# AutonomousBot_Shield.net
KiCad netlist of a schematic drawn in EAGLE
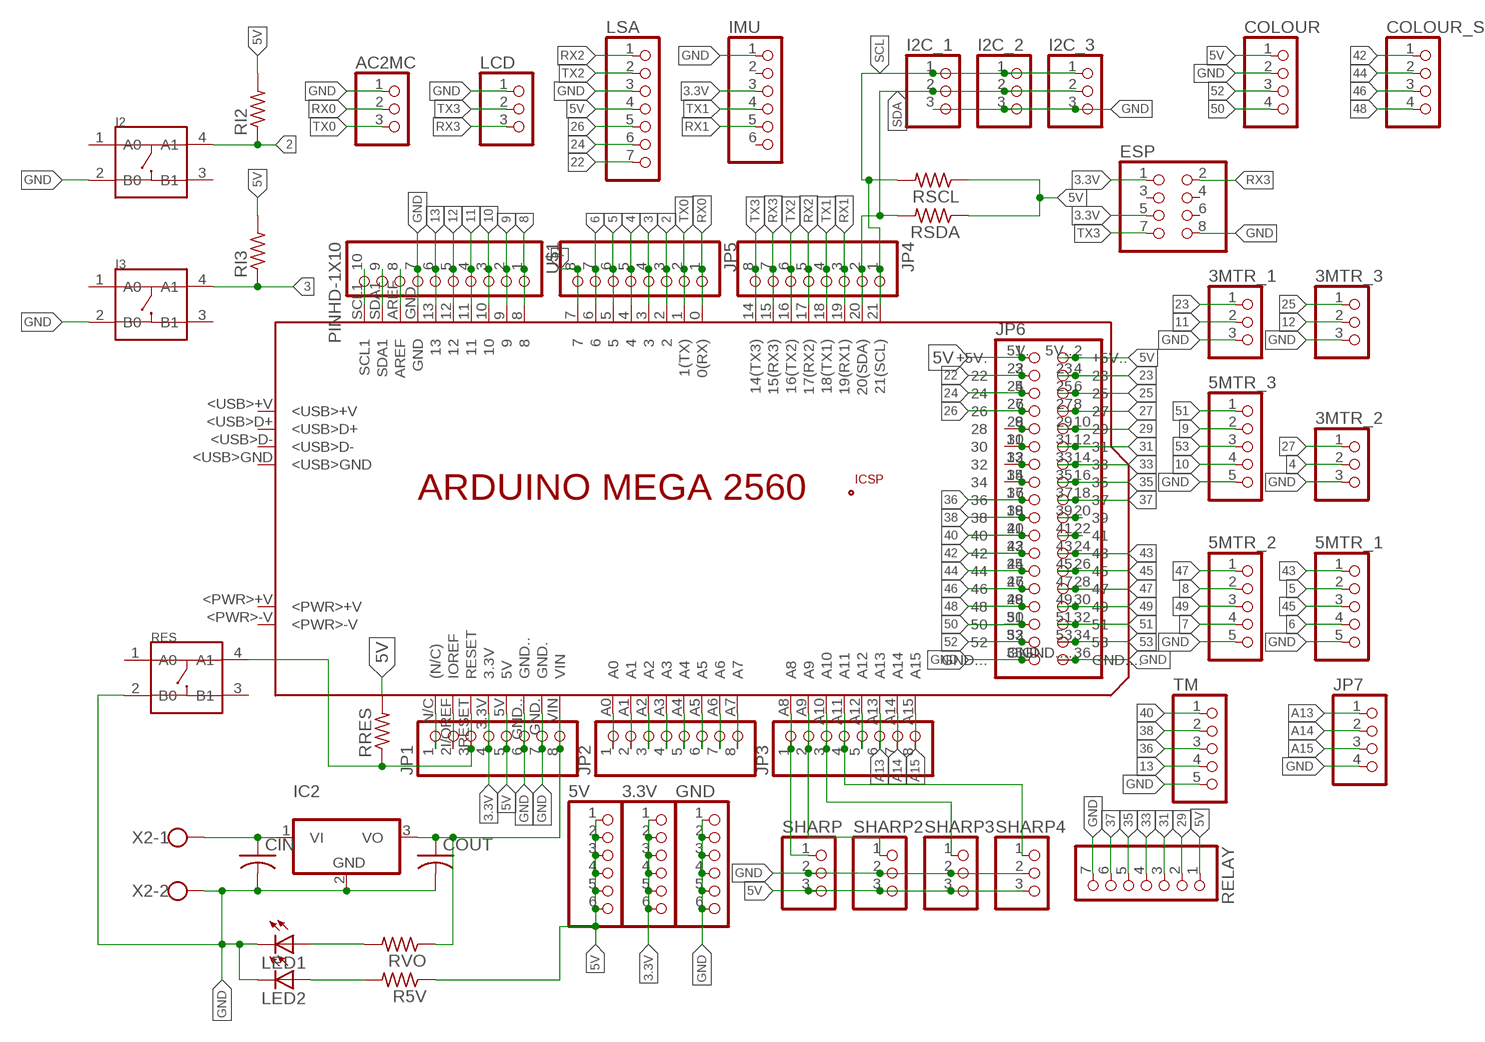
[diagram p0: schematic, sheet 1]

(export (version "E")
  (design (tool "Eeschema 10.0.6"))
  (components
    (comp (ref "3.3V")
      (value "PINHD-1X6")
      (footprint "eagle-import:1X06")
      (libsource (lib "eagle-import") (part "PINHD-1X6"))
    )
    (comp (ref "3MTR_1")
      (value "PINHD-1X3")
      (footprint "eagle-import:1X03")
      (libsource (lib "eagle-import") (part "pinhead_325_PINHD-1X3"))
    )
    (comp (ref "3MTR_2")
      (value "PINHD-1X3")
      (footprint "eagle-import:1X03")
      (libsource (lib "eagle-import") (part "pinhead_325_PINHD-1X3"))
    )
    (comp (ref "3MTR_3")
      (value "PINHD-1X3")
      (footprint "eagle-import:1X03")
      (libsource (lib "eagle-import") (part "pinhead_325_PINHD-1X3"))
    )
    (comp (ref "5MTR_1")
      (value "PINHD-1X5")
      (footprint "eagle-import:1X05")
      (libsource (lib "eagle-import") (part "pinhead_325_PINHD-1X5"))
    )
    (comp (ref "5MTR_2")
      (value "PINHD-1X5")
      (footprint "eagle-import:1X05")
      (libsource (lib "eagle-import") (part "pinhead_325_PINHD-1X5"))
    )
    (comp (ref "5MTR_3")
      (value "PINHD-1X5")
      (footprint "eagle-import:1X05")
      (libsource (lib "eagle-import") (part "pinhead_325_PINHD-1X5"))
    )
    (comp (ref "5V")
      (value "PINHD-1X6")
      (footprint "eagle-import:1X06")
      (libsource (lib "eagle-import") (part "PINHD-1X6"))
    )
    (comp (ref "AC2MC")
      (value "PINHD-1X3")
      (footprint "eagle-import:1X03")
      (libsource (lib "eagle-import") (part "PINHD-1X3"))
    )
    (comp (ref "CIN")
      (value "C-US025-024X044")
      (footprint "eagle-import:C025-024X044")
      (libsource (lib "eagle-import") (part "C-US025-024X044"))
    )
    (comp (ref "COLOUR")
      (value "PINHD-1X4")
      (footprint "eagle-import:1X04")
      (libsource (lib "eagle-import") (part "PINHD-1X4"))
    )
    (comp (ref "COLOUR_S")
      (value "PINHD-1X4")
      (footprint "eagle-import:1X04")
      (libsource (lib "eagle-import") (part "PINHD-1X4"))
    )
    (comp (ref "COUT")
      (value "C-US025-024X044")
      (footprint "eagle-import:C025-024X044")
      (libsource (lib "eagle-import") (part "C-US025-024X044"))
    )
    (comp (ref "ESP")
      (value "PINHD-2X4")
      (footprint "eagle-import:2X04")
      (libsource (lib "eagle-import") (part "PINHD-2X4"))
    )
    (comp (ref "GND")
      (value "PINHD-1X6")
      (footprint "eagle-import:1X06")
      (libsource (lib "eagle-import") (part "PINHD-1X6"))
    )
    (comp (ref "I2")
      (value "DIP-SWITCH-TACTILE-SPST-NO/TS-1109(4P-D6.0MM)'TS-1109'")
      (footprint "eagle-import:SW4-6.0X6.0X5.0MM")
      (libsource (lib "eagle-import") (part "DIP-SWITCH-TACTILE-SPST-NO/TS-1109(4P-D6.0MM)'TS-1109'"))
    )
    (comp (ref "I2C_1")
      (value "PINHD-1X3")
      (footprint "eagle-import:1X03")
      (libsource (lib "eagle-import") (part "PINHD-1X3"))
    )
    (comp (ref "I2C_2")
      (value "PINHD-1X3")
      (footprint "eagle-import:1X03")
      (libsource (lib "eagle-import") (part "PINHD-1X3"))
    )
    (comp (ref "I2C_3")
      (value "PINHD-1X3")
      (footprint "eagle-import:1X03")
      (libsource (lib "eagle-import") (part "PINHD-1X3"))
    )
    (comp (ref "I3")
      (value "DIP-SWITCH-TACTILE-SPST-NO/TS-1109(4P-D6.0MM)'TS-1109'")
      (footprint "eagle-import:SW4-6.0X6.0X5.0MM")
      (libsource (lib "eagle-import") (part "DIP-SWITCH-TACTILE-SPST-NO/TS-1109(4P-D6.0MM)'TS-1109'"))
    )
    (comp (ref "IC2")
      (value "7812TV")
      (footprint "eagle-import:TO220V")
      (libsource (lib "eagle-import") (part "78TV12"))
    )
    (comp (ref "IMU")
      (value "PINHD-1X6")
      (footprint "eagle-import:1X06")
      (libsource (lib "eagle-import") (part "PINHD-1X6"))
    )
    (comp (ref "JP1")
      (value "PINHD-1X8BIG")
      (footprint "eagle-import:1X08-BIG")
      (libsource (lib "eagle-import") (part "PINHD-1X8BIG"))
    )
    (comp (ref "JP2")
      (value "PINHD-1X8BIG")
      (footprint "eagle-import:1X08-BIG")
      (libsource (lib "eagle-import") (part "PINHD-1X8BIG"))
    )
    (comp (ref "JP3")
      (value "PINHD-1X8BIG")
      (footprint "eagle-import:1X08-BIG")
      (libsource (lib "eagle-import") (part "PINHD-1X8BIG"))
    )
    (comp (ref "JP4")
      (value "PINHD-1X8BIG")
      (footprint "eagle-import:1X08-BIG")
      (libsource (lib "eagle-import") (part "PINHD-1X8BIG"))
    )
    (comp (ref "JP5")
      (value "PINHD-1X8BIG")
      (footprint "eagle-import:1X08-BIG")
      (libsource (lib "eagle-import") (part "PINHD-1X8BIG"))
    )
    (comp (ref "JP6")
      (value "PINHD-2X18")
      (footprint "eagle-import:2X18")
      (libsource (lib "eagle-import") (part "PINHD-2X18"))
    )
    (comp (ref "JP7")
      (value "PINHD-1X4")
      (footprint "eagle-import:1X04")
      (libsource (lib "eagle-import") (part "PINHD-1X4"))
    )
    (comp (ref "LCD")
      (value "PINHD-1X3")
      (footprint "eagle-import:1X03")
      (libsource (lib "eagle-import") (part "PINHD-1X3"))
    )
    (comp (ref "LED1")
      (value "LED5MM")
      (footprint "eagle-import:LED5MM")
      (libsource (lib "eagle-import") (part "LED5MM"))
    )
    (comp (ref "LED2")
      (value "LED5MM")
      (footprint "eagle-import:LED5MM")
      (libsource (lib "eagle-import") (part "LED5MM"))
    )
    (comp (ref "LSA")
      (value "PINHD-1X7")
      (footprint "eagle-import:1X07")
      (libsource (lib "eagle-import") (part "PINHD-1X7"))
    )
    (comp (ref "PCB1")
      (value "ARDUINO_MEGA2560")
      (footprint "eagle-import:ARDUINO_MEGA2560")
      (libsource (lib "eagle-import") (part "ARDUINO_MEGA2560"))
    )
    (comp (ref "R5V")
      (value "R-US_0207/7")
      (footprint "eagle-import:0207_7")
      (libsource (lib "eagle-import") (part "R-US_0207/7"))
    )
    (comp (ref "RELAY")
      (value "PINHD-1X7")
      (footprint "eagle-import:1X07")
      (libsource (lib "eagle-import") (part "PINHD-1X7"))
    )
    (comp (ref "RES")
      (value "DIP-SWITCH-TACTILE-SPST-NO/TS-1109(4P-D6.0MM)'TS-1109'")
      (footprint "eagle-import:SW4-6.0X6.0X5.0MM")
      (libsource (lib "eagle-import") (part "DIP-SWITCH-TACTILE-SPST-NO/TS-1109(4P-D6.0MM)'TS-1109'"))
    )
    (comp (ref "RI2")
      (value "R-US_0207/7")
      (footprint "eagle-import:0207_7")
      (libsource (lib "eagle-import") (part "R-US_0207/7"))
    )
    (comp (ref "RI3")
      (value "R-US_0207/7")
      (footprint "eagle-import:0207_7")
      (libsource (lib "eagle-import") (part "R-US_0207/7"))
    )
    (comp (ref "RRES")
      (value "R-US_0207/7")
      (footprint "eagle-import:0207_7")
      (libsource (lib "eagle-import") (part "R-US_0207/7"))
    )
    (comp (ref "RSCL")
      (value "R-US_0207/7")
      (footprint "eagle-import:0207_7")
      (libsource (lib "eagle-import") (part "R-US_0207/7"))
    )
    (comp (ref "RSDA")
      (value "R-US_0207/7")
      (footprint "eagle-import:0207_7")
      (libsource (lib "eagle-import") (part "R-US_0207/7"))
    )
    (comp (ref "RVO")
      (value "R-US_0207/7")
      (footprint "eagle-import:0207_7")
      (libsource (lib "eagle-import") (part "R-US_0207/7"))
    )
    (comp (ref "SHARP")
      (value "PINHD-1X3")
      (footprint "eagle-import:1X03")
      (libsource (lib "eagle-import") (part "PINHD-1X3"))
    )
    (comp (ref "SHARP2")
      (value "PINHD-1X3")
      (footprint "eagle-import:1X03")
      (libsource (lib "eagle-import") (part "PINHD-1X3"))
    )
    (comp (ref "SHARP3")
      (value "PINHD-1X3")
      (footprint "eagle-import:1X03")
      (libsource (lib "eagle-import") (part "PINHD-1X3"))
    )
    (comp (ref "SHARP4")
      (value "PINHD-1X3")
      (footprint "eagle-import:1X03")
      (libsource (lib "eagle-import") (part "PINHD-1X3"))
    )
    (comp (ref "TM")
      (value "PINHD-1X5")
      (footprint "eagle-import:1X05")
      (libsource (lib "eagle-import") (part "PINHD-1X5"))
    )
    (comp (ref "U$1")
      (value "PINHD-1X10")
      (footprint "eagle-import:1X10-BIG")
      (libsource (lib "eagle-import") (part "PINHD-1X10"))
    )
    (comp (ref "X2")
      (value "W237-102")
      (footprint "eagle-import:W237-102")
      (fields (field (name "MPN") "237-102"))
      (libsource (lib "eagle-import") (part "W237-102"))
    )
  )
  (nets
    (net (code "1") (name "2") (class "Default")
      (node (ref "I2") (pin "4") (pinfunction "A1_4") (pintype "bidirectional"))
      (node (ref "JP5") (pin "3") (pinfunction "3_3") (pintype "passive"))
      (node (ref "PCB1") (pin "2") (pinfunction "2_2") (pintype "bidirectional"))
      (node (ref "RI2") (pin "1") (pinfunction "1_1") (pintype "passive"))
    )
    (net (code "2") (name "3") (class "Default")
      (node (ref "I3") (pin "4") (pinfunction "A1_4") (pintype "bidirectional"))
      (node (ref "JP5") (pin "4") (pinfunction "4_4") (pintype "passive"))
      (node (ref "PCB1") (pin "3") (pinfunction "3_3") (pintype "bidirectional"))
      (node (ref "RI3") (pin "1") (pinfunction "1_1") (pintype "passive"))
    )
    (net (code "3") (name "3.3V") (class "Default")
      (node (ref "3.3V") (pin "1") (pinfunction "1_1") (pintype "passive"))
      (node (ref "3.3V") (pin "2") (pinfunction "2_2") (pintype "passive"))
      (node (ref "3.3V") (pin "3") (pinfunction "3_3") (pintype "passive"))
      (node (ref "3.3V") (pin "4") (pinfunction "4_4") (pintype "passive"))
      (node (ref "3.3V") (pin "5") (pinfunction "5_5") (pintype "passive"))
      (node (ref "3.3V") (pin "6") (pinfunction "6_6") (pintype "passive"))
      (node (ref "ESP") (pin "1") (pinfunction "1_1") (pintype "passive"))
      (node (ref "ESP") (pin "5") (pinfunction "5_5") (pintype "passive"))
      (node (ref "IMU") (pin "3") (pinfunction "3_3") (pintype "passive"))
      (node (ref "JP1") (pin "4") (pinfunction "4_4") (pintype "passive"))
      (node (ref "PCB1") (pin "3.3V") (pinfunction "3.3V_3.3V") (pintype "bidirectional"))
    )
    (net (code "4") (name "4") (class "Default")
      (node (ref "3MTR_2") (pin "2") (pinfunction "2_2") (pintype "passive"))
      (node (ref "JP5") (pin "5") (pinfunction "5_5") (pintype "passive"))
      (node (ref "PCB1") (pin "4") (pinfunction "4_4") (pintype "bidirectional"))
    )
    (net (code "5") (name "5") (class "Default")
      (node (ref "5MTR_1") (pin "2") (pinfunction "2_2") (pintype "passive"))
      (node (ref "JP5") (pin "6") (pinfunction "6_6") (pintype "passive"))
      (node (ref "PCB1") (pin "5") (pinfunction "5_5") (pintype "bidirectional"))
    )
    (net (code "6") (name "5V") (class "Default")
      (node (ref "5V") (pin "1") (pinfunction "1_1") (pintype "passive"))
      (node (ref "5V") (pin "2") (pinfunction "2_2") (pintype "passive"))
      (node (ref "5V") (pin "3") (pinfunction "3_3") (pintype "passive"))
      (node (ref "5V") (pin "4") (pinfunction "4_4") (pintype "passive"))
      (node (ref "5V") (pin "5") (pinfunction "5_5") (pintype "passive"))
      (node (ref "5V") (pin "6") (pinfunction "6_6") (pintype "passive"))
      (node (ref "COLOUR") (pin "1") (pinfunction "1_1") (pintype "passive"))
      (node (ref "JP1") (pin "5") (pinfunction "5_5") (pintype "passive"))
      (node (ref "JP6") (pin "1") (pinfunction "1_1") (pintype "passive"))
      (node (ref "JP6") (pin "2") (pinfunction "2_2") (pintype "passive"))
      (node (ref "LSA") (pin "4") (pinfunction "4_4") (pintype "passive"))
      (node (ref "PCB1") (pin "5V") (pinfunction "5V_5V") (pintype "bidirectional"))
      (node (ref "PCB1") (pin "5V.") (pinfunction "+5V._5V.") (pintype "bidirectional"))
      (node (ref "PCB1") (pin "5V..") (pinfunction "+5V.._5V..") (pintype "bidirectional"))
      (node (ref "R5V") (pin "1") (pinfunction "1_1") (pintype "passive"))
      (node (ref "RELAY") (pin "1") (pinfunction "1_1") (pintype "passive"))
      (node (ref "RI2") (pin "2") (pinfunction "2_2") (pintype "passive"))
      (node (ref "RI3") (pin "2") (pinfunction "2_2") (pintype "passive"))
      (node (ref "RRES") (pin "2") (pinfunction "2_2") (pintype "passive"))
      (node (ref "RSCL") (pin "1") (pinfunction "1_1") (pintype "passive"))
      (node (ref "RSDA") (pin "1") (pinfunction "1_1") (pintype "passive"))
      (node (ref "SHARP") (pin "3") (pinfunction "3_3") (pintype "passive"))
      (node (ref "SHARP2") (pin "3") (pinfunction "3_3") (pintype "passive"))
      (node (ref "SHARP3") (pin "3") (pinfunction "3_3") (pintype "passive"))
      (node (ref "SHARP4") (pin "3") (pinfunction "3_3") (pintype "passive"))
    )
    (net (code "7") (name "6") (class "Default")
      (node (ref "5MTR_1") (pin "4") (pinfunction "4_4") (pintype "passive"))
      (node (ref "JP5") (pin "7") (pinfunction "7_7") (pintype "passive"))
      (node (ref "PCB1") (pin "6") (pinfunction "6_6") (pintype "bidirectional"))
    )
    (net (code "8") (name "7") (class "Default")
      (node (ref "5MTR_2") (pin "4") (pinfunction "4_4") (pintype "passive"))
      (node (ref "JP5") (pin "8") (pinfunction "8_8") (pintype "passive"))
      (node (ref "PCB1") (pin "7") (pinfunction "7_7") (pintype "bidirectional"))
    )
    (net (code "9") (name "8") (class "Default")
      (node (ref "5MTR_2") (pin "2") (pinfunction "2_2") (pintype "passive"))
      (node (ref "PCB1") (pin "8") (pinfunction "8_8") (pintype "bidirectional"))
      (node (ref "U$1") (pin "1") (pinfunction "1_1") (pintype "passive"))
    )
    (net (code "10") (name "9") (class "Default")
      (node (ref "5MTR_3") (pin "2") (pinfunction "2_2") (pintype "passive"))
      (node (ref "PCB1") (pin "9") (pinfunction "9_9") (pintype "bidirectional"))
      (node (ref "U$1") (pin "2") (pinfunction "2_2") (pintype "passive"))
    )
    (net (code "11") (name "10") (class "Default")
      (node (ref "5MTR_3") (pin "4") (pinfunction "4_4") (pintype "passive"))
      (node (ref "PCB1") (pin "10") (pinfunction "10_10") (pintype "bidirectional"))
      (node (ref "U$1") (pin "3") (pinfunction "3_3") (pintype "passive"))
    )
    (net (code "12") (name "11") (class "Default")
      (node (ref "3MTR_1") (pin "2") (pinfunction "2_2") (pintype "passive"))
      (node (ref "PCB1") (pin "11") (pinfunction "11_11") (pintype "bidirectional"))
      (node (ref "U$1") (pin "4") (pinfunction "4_4") (pintype "passive"))
    )
    (net (code "13") (name "12") (class "Default")
      (node (ref "3MTR_3") (pin "2") (pinfunction "2_2") (pintype "passive"))
      (node (ref "PCB1") (pin "12") (pinfunction "12_12") (pintype "bidirectional"))
      (node (ref "U$1") (pin "5") (pinfunction "5_5") (pintype "passive"))
    )
    (net (code "14") (name "13") (class "Default")
      (node (ref "PCB1") (pin "13") (pinfunction "13_13") (pintype "bidirectional"))
      (node (ref "TM") (pin "4") (pinfunction "4_4") (pintype "passive"))
      (node (ref "U$1") (pin "6") (pinfunction "6_6") (pintype "passive"))
    )
    (net (code "15") (name "22") (class "Default")
      (node (ref "JP6") (pin "3") (pinfunction "3_3") (pintype "passive"))
      (node (ref "LSA") (pin "7") (pinfunction "7_7") (pintype "passive"))
      (node (ref "PCB1") (pin "22") (pinfunction "22_22") (pintype "bidirectional"))
    )
    (net (code "16") (name "23") (class "Default")
      (node (ref "3MTR_1") (pin "1") (pinfunction "1_1") (pintype "passive"))
      (node (ref "JP6") (pin "4") (pinfunction "4_4") (pintype "passive"))
      (node (ref "PCB1") (pin "23") (pinfunction "23_23") (pintype "bidirectional"))
    )
    (net (code "17") (name "24") (class "Default")
      (node (ref "JP6") (pin "5") (pinfunction "5_5") (pintype "passive"))
      (node (ref "LSA") (pin "6") (pinfunction "6_6") (pintype "passive"))
      (node (ref "PCB1") (pin "24") (pinfunction "24_24") (pintype "bidirectional"))
    )
    (net (code "18") (name "25") (class "Default")
      (node (ref "3MTR_3") (pin "1") (pinfunction "1_1") (pintype "passive"))
      (node (ref "JP6") (pin "6") (pinfunction "6_6") (pintype "passive"))
      (node (ref "PCB1") (pin "25") (pinfunction "25_25") (pintype "bidirectional"))
    )
    (net (code "19") (name "26") (class "Default")
      (node (ref "JP6") (pin "7") (pinfunction "7_7") (pintype "passive"))
      (node (ref "LSA") (pin "5") (pinfunction "5_5") (pintype "passive"))
      (node (ref "PCB1") (pin "26") (pinfunction "26_26") (pintype "bidirectional"))
    )
    (net (code "20") (name "27") (class "Default")
      (node (ref "3MTR_2") (pin "1") (pinfunction "1_1") (pintype "passive"))
      (node (ref "JP6") (pin "8") (pinfunction "8_8") (pintype "passive"))
      (node (ref "PCB1") (pin "27") (pinfunction "27_27") (pintype "bidirectional"))
    )
    (net (code "21") (name "29") (class "Default")
      (node (ref "JP6") (pin "10") (pinfunction "10_10") (pintype "passive"))
      (node (ref "PCB1") (pin "29") (pinfunction "29_29") (pintype "bidirectional"))
      (node (ref "RELAY") (pin "2") (pinfunction "2_2") (pintype "passive"))
    )
    (net (code "22") (name "31") (class "Default")
      (node (ref "JP6") (pin "12") (pinfunction "12_12") (pintype "passive"))
      (node (ref "PCB1") (pin "31") (pinfunction "31_31") (pintype "bidirectional"))
      (node (ref "RELAY") (pin "3") (pinfunction "3_3") (pintype "passive"))
    )
    (net (code "23") (name "33") (class "Default")
      (node (ref "JP6") (pin "14") (pinfunction "14_14") (pintype "passive"))
      (node (ref "PCB1") (pin "33") (pinfunction "33_33") (pintype "bidirectional"))
      (node (ref "RELAY") (pin "4") (pinfunction "4_4") (pintype "passive"))
    )
    (net (code "24") (name "35") (class "Default")
      (node (ref "JP6") (pin "16") (pinfunction "16_16") (pintype "passive"))
      (node (ref "PCB1") (pin "35") (pinfunction "35_35") (pintype "bidirectional"))
      (node (ref "RELAY") (pin "5") (pinfunction "5_5") (pintype "passive"))
    )
    (net (code "25") (name "36") (class "Default")
      (node (ref "JP6") (pin "17") (pinfunction "17_17") (pintype "passive"))
      (node (ref "PCB1") (pin "36") (pinfunction "36_36") (pintype "bidirectional"))
      (node (ref "TM") (pin "3") (pinfunction "3_3") (pintype "passive"))
    )
    (net (code "26") (name "37") (class "Default")
      (node (ref "JP6") (pin "18") (pinfunction "18_18") (pintype "passive"))
      (node (ref "PCB1") (pin "37") (pinfunction "37_37") (pintype "bidirectional"))
      (node (ref "RELAY") (pin "6") (pinfunction "6_6") (pintype "passive"))
    )
    (net (code "27") (name "38") (class "Default")
      (node (ref "JP6") (pin "19") (pinfunction "19_19") (pintype "passive"))
      (node (ref "PCB1") (pin "38") (pinfunction "38_38") (pintype "bidirectional"))
      (node (ref "TM") (pin "2") (pinfunction "2_2") (pintype "passive"))
    )
    (net (code "28") (name "40") (class "Default")
      (node (ref "JP6") (pin "21") (pinfunction "21_21") (pintype "passive"))
      (node (ref "PCB1") (pin "40") (pinfunction "40_40") (pintype "bidirectional"))
      (node (ref "TM") (pin "1") (pinfunction "1_1") (pintype "passive"))
    )
    (net (code "29") (name "42") (class "Default")
      (node (ref "COLOUR_S") (pin "1") (pinfunction "1_1") (pintype "passive"))
      (node (ref "JP6") (pin "23") (pinfunction "23_23") (pintype "passive"))
      (node (ref "PCB1") (pin "42") (pinfunction "42_42") (pintype "bidirectional"))
    )
    (net (code "30") (name "43") (class "Default")
      (node (ref "5MTR_1") (pin "1") (pinfunction "1_1") (pintype "passive"))
      (node (ref "JP6") (pin "24") (pinfunction "24_24") (pintype "passive"))
      (node (ref "PCB1") (pin "43") (pinfunction "43_43") (pintype "bidirectional"))
    )
    (net (code "31") (name "44") (class "Default")
      (node (ref "COLOUR_S") (pin "2") (pinfunction "2_2") (pintype "passive"))
      (node (ref "JP6") (pin "25") (pinfunction "25_25") (pintype "passive"))
      (node (ref "PCB1") (pin "44") (pinfunction "44_44") (pintype "bidirectional"))
    )
    (net (code "32") (name "45") (class "Default")
      (node (ref "5MTR_1") (pin "3") (pinfunction "3_3") (pintype "passive"))
      (node (ref "JP6") (pin "26") (pinfunction "26_26") (pintype "passive"))
      (node (ref "PCB1") (pin "45") (pinfunction "45_45") (pintype "bidirectional"))
    )
    (net (code "33") (name "46") (class "Default")
      (node (ref "COLOUR_S") (pin "3") (pinfunction "3_3") (pintype "passive"))
      (node (ref "JP6") (pin "27") (pinfunction "27_27") (pintype "passive"))
      (node (ref "PCB1") (pin "46") (pinfunction "46_46") (pintype "bidirectional"))
    )
    (net (code "34") (name "47") (class "Default")
      (node (ref "5MTR_2") (pin "1") (pinfunction "1_1") (pintype "passive"))
      (node (ref "JP6") (pin "28") (pinfunction "28_28") (pintype "passive"))
      (node (ref "PCB1") (pin "47") (pinfunction "47_47") (pintype "bidirectional"))
    )
    (net (code "35") (name "48") (class "Default")
      (node (ref "COLOUR_S") (pin "4") (pinfunction "4_4") (pintype "passive"))
      (node (ref "JP6") (pin "29") (pinfunction "29_29") (pintype "passive"))
      (node (ref "PCB1") (pin "48") (pinfunction "48_48") (pintype "bidirectional"))
    )
    (net (code "36") (name "49") (class "Default")
      (node (ref "5MTR_2") (pin "3") (pinfunction "3_3") (pintype "passive"))
      (node (ref "JP6") (pin "30") (pinfunction "30_30") (pintype "passive"))
      (node (ref "PCB1") (pin "49") (pinfunction "49_49") (pintype "bidirectional"))
    )
    (net (code "37") (name "50") (class "Default")
      (node (ref "COLOUR") (pin "4") (pinfunction "4_4") (pintype "passive"))
      (node (ref "JP6") (pin "31") (pinfunction "31_31") (pintype "passive"))
      (node (ref "PCB1") (pin "50") (pinfunction "50_50") (pintype "bidirectional"))
    )
    (net (code "38") (name "51") (class "Default")
      (node (ref "5MTR_3") (pin "1") (pinfunction "1_1") (pintype "passive"))
      (node (ref "JP6") (pin "32") (pinfunction "32_32") (pintype "passive"))
      (node (ref "PCB1") (pin "51") (pinfunction "51_51") (pintype "bidirectional"))
    )
    (net (code "39") (name "52") (class "Default")
      (node (ref "COLOUR") (pin "3") (pinfunction "3_3") (pintype "passive"))
      (node (ref "JP6") (pin "33") (pinfunction "33_33") (pintype "passive"))
      (node (ref "PCB1") (pin "52") (pinfunction "52_52") (pintype "bidirectional"))
    )
    (net (code "40") (name "53") (class "Default")
      (node (ref "5MTR_3") (pin "3") (pinfunction "3_3") (pintype "passive"))
      (node (ref "JP6") (pin "34") (pinfunction "34_34") (pintype "passive"))
      (node (ref "PCB1") (pin "53") (pinfunction "53_53") (pintype "bidirectional"))
    )
    (net (code "41") (name "A13") (class "Default")
      (node (ref "JP3") (pin "6") (pinfunction "6_6") (pintype "passive"))
      (node (ref "JP7") (pin "1") (pinfunction "1_1") (pintype "passive"))
      (node (ref "PCB1") (pin "A13") (pinfunction "A13_A13") (pintype "bidirectional"))
    )
    (net (code "42") (name "A14") (class "Default")
      (node (ref "JP3") (pin "7") (pinfunction "7_7") (pintype "passive"))
      (node (ref "JP7") (pin "2") (pinfunction "2_2") (pintype "passive"))
      (node (ref "PCB1") (pin "A14") (pinfunction "A14_A14") (pintype "bidirectional"))
    )
    (net (code "43") (name "A15") (class "Default")
      (node (ref "JP3") (pin "8") (pinfunction "8_8") (pintype "passive"))
      (node (ref "JP7") (pin "3") (pinfunction "3_3") (pintype "passive"))
      (node (ref "PCB1") (pin "A15") (pinfunction "A15_A15") (pintype "bidirectional"))
    )
    (net (code "44") (name "GND") (class "Default")
      (node (ref "3MTR_1") (pin "3") (pinfunction "3_3") (pintype "passive"))
      (node (ref "3MTR_2") (pin "3") (pinfunction "3_3") (pintype "passive"))
      (node (ref "3MTR_3") (pin "3") (pinfunction "3_3") (pintype "passive"))
      (node (ref "5MTR_1") (pin "5") (pinfunction "5_5") (pintype "passive"))
      (node (ref "5MTR_2") (pin "5") (pinfunction "5_5") (pintype "passive"))
      (node (ref "5MTR_3") (pin "5") (pinfunction "5_5") (pintype "passive"))
      (node (ref "AC2MC") (pin "1") (pinfunction "1_1") (pintype "passive"))
      (node (ref "CIN") (pin "2") (pinfunction "2_2") (pintype "passive"))
      (node (ref "COLOUR") (pin "2") (pinfunction "2_2") (pintype "passive"))
      (node (ref "COUT") (pin "2") (pinfunction "2_2") (pintype "passive"))
      (node (ref "ESP") (pin "8") (pinfunction "8_8") (pintype "passive"))
      (node (ref "GND") (pin "1") (pinfunction "1_1") (pintype "passive"))
      (node (ref "GND") (pin "2") (pinfunction "2_2") (pintype "passive"))
      (node (ref "GND") (pin "3") (pinfunction "3_3") (pintype "passive"))
      (node (ref "GND") (pin "4") (pinfunction "4_4") (pintype "passive"))
      (node (ref "GND") (pin "5") (pinfunction "5_5") (pintype "passive"))
      (node (ref "GND") (pin "6") (pinfunction "6_6") (pintype "passive"))
      (node (ref "I2") (pin "2") (pinfunction "B0_2") (pintype "bidirectional"))
      (node (ref "I2C_1") (pin "3") (pinfunction "3_3") (pintype "passive"))
      (node (ref "I2C_2") (pin "3") (pinfunction "3_3") (pintype "passive"))
      (node (ref "I2C_3") (pin "3") (pinfunction "3_3") (pintype "passive"))
      (node (ref "I3") (pin "2") (pinfunction "B0_2") (pintype "bidirectional"))
      (node (ref "IC2") (pin "2") (pinfunction "GND_2") (pintype "passive"))
      (node (ref "IMU") (pin "1") (pinfunction "1_1") (pintype "passive"))
      (node (ref "JP1") (pin "6") (pinfunction "6_6") (pintype "passive"))
      (node (ref "JP1") (pin "7") (pinfunction "7_7") (pintype "passive"))
      (node (ref "JP6") (pin "35") (pinfunction "35_35") (pintype "passive"))
      (node (ref "JP6") (pin "36") (pinfunction "36_36") (pintype "passive"))
      (node (ref "JP7") (pin "4") (pinfunction "4_4") (pintype "passive"))
      (node (ref "LCD") (pin "1") (pinfunction "1_1") (pintype "passive"))
      (node (ref "LED1") (pin "K") (pinfunction "C_K") (pintype "passive"))
      (node (ref "LED2") (pin "K") (pinfunction "C_K") (pintype "passive"))
      (node (ref "LSA") (pin "3") (pinfunction "3_3") (pintype "passive"))
      (node (ref "PCB1") (pin "GND") (pinfunction "GND_GND") (pintype "bidirectional"))
      (node (ref "PCB1") (pin "GND.") (pinfunction "GND._GND.") (pintype "bidirectional"))
      (node (ref "PCB1") (pin "GND..") (pinfunction "GND.._GND..") (pintype "bidirectional"))
      (node (ref "PCB1") (pin "GND...") (pinfunction "GND..._GND...") (pintype "bidirectional"))
      (node (ref "PCB1") (pin "GND....") (pinfunction "GND...._GND....") (pintype "bidirectional"))
      (node (ref "RELAY") (pin "7") (pinfunction "7_7") (pintype "passive"))
      (node (ref "RES") (pin "2") (pinfunction "B0_2") (pintype "bidirectional"))
      (node (ref "SHARP") (pin "2") (pinfunction "2_2") (pintype "passive"))
      (node (ref "SHARP2") (pin "2") (pinfunction "2_2") (pintype "passive"))
      (node (ref "SHARP3") (pin "2") (pinfunction "2_2") (pintype "passive"))
      (node (ref "SHARP4") (pin "2") (pinfunction "2_2") (pintype "passive"))
      (node (ref "TM") (pin "5") (pinfunction "5_5") (pintype "passive"))
      (node (ref "U$1") (pin "7") (pinfunction "7_7") (pintype "passive"))
      (node (ref "X2") (pin "2") (pinfunction "KL_2") (pintype "passive"))
    )
    (net (code "45") (name "Net-(IC2-VI)") (class "Default")
      (node (ref "CIN") (pin "1") (pinfunction "1_1") (pintype "passive"))
      (node (ref "IC2") (pin "1") (pinfunction "VI_1") (pintype "input"))
      (node (ref "X2") (pin "1") (pinfunction "KL_1") (pintype "passive"))
    )
    (net (code "46") (name "Net-(IC2-VO)") (class "Default")
      (node (ref "COUT") (pin "1") (pinfunction "1_1") (pintype "passive"))
      (node (ref "IC2") (pin "3") (pinfunction "VO_3") (pintype "passive"))
      (node (ref "JP1") (pin "8") (pinfunction "8_8") (pintype "passive"))
      (node (ref "PCB1") (pin "VIN") (pinfunction "VIN_VIN") (pintype "bidirectional"))
      (node (ref "RVO") (pin "1") (pinfunction "1_1") (pintype "passive"))
    )
    (net (code "47") (name "Net-(JP2-Pad1)") (class "Default")
      (node (ref "JP2") (pin "1") (pinfunction "1_1") (pintype "passive"))
      (node (ref "PCB1") (pin "A0") (pinfunction "A0_A0") (pintype "bidirectional"))
    )
    (net (code "48") (name "Net-(JP2-Pad2)") (class "Default")
      (node (ref "JP2") (pin "2") (pinfunction "2_2") (pintype "passive"))
      (node (ref "PCB1") (pin "A1") (pinfunction "A1_A1") (pintype "bidirectional"))
    )
    (net (code "49") (name "Net-(JP2-Pad3)") (class "Default")
      (node (ref "JP2") (pin "3") (pinfunction "3_3") (pintype "passive"))
      (node (ref "PCB1") (pin "A2") (pinfunction "A2_A2") (pintype "bidirectional"))
    )
    (net (code "50") (name "Net-(JP2-Pad4)") (class "Default")
      (node (ref "JP2") (pin "4") (pinfunction "4_4") (pintype "passive"))
      (node (ref "PCB1") (pin "A3") (pinfunction "A3_A3") (pintype "bidirectional"))
    )
    (net (code "51") (name "Net-(JP2-Pad5)") (class "Default")
      (node (ref "JP2") (pin "5") (pinfunction "5_5") (pintype "passive"))
      (node (ref "PCB1") (pin "A4") (pinfunction "A4_A4") (pintype "bidirectional"))
    )
    (net (code "52") (name "Net-(JP2-Pad6)") (class "Default")
      (node (ref "JP2") (pin "6") (pinfunction "6_6") (pintype "passive"))
      (node (ref "PCB1") (pin "A5") (pinfunction "A5_A5") (pintype "bidirectional"))
    )
    (net (code "53") (name "Net-(JP2-Pad7)") (class "Default")
      (node (ref "JP2") (pin "7") (pinfunction "7_7") (pintype "passive"))
      (node (ref "PCB1") (pin "A6") (pinfunction "A6_A6") (pintype "bidirectional"))
    )
    (net (code "54") (name "Net-(JP2-Pad8)") (class "Default")
      (node (ref "JP2") (pin "8") (pinfunction "8_8") (pintype "passive"))
      (node (ref "PCB1") (pin "A7") (pinfunction "A7_A7") (pintype "bidirectional"))
    )
    (net (code "55") (name "Net-(JP3-Pad1)") (class "Default")
      (node (ref "JP3") (pin "1") (pinfunction "1_1") (pintype "passive"))
      (node (ref "PCB1") (pin "A8") (pinfunction "A8_A8") (pintype "bidirectional"))
      (node (ref "SHARP") (pin "1") (pinfunction "1_1") (pintype "passive"))
    )
    (net (code "56") (name "Net-(JP3-Pad2)") (class "Default")
      (node (ref "JP3") (pin "2") (pinfunction "2_2") (pintype "passive"))
      (node (ref "PCB1") (pin "A9") (pinfunction "A9_A9") (pintype "bidirectional"))
      (node (ref "SHARP2") (pin "1") (pinfunction "1_1") (pintype "passive"))
    )
    (net (code "57") (name "Net-(JP3-Pad3)") (class "Default")
      (node (ref "JP3") (pin "3") (pinfunction "3_3") (pintype "passive"))
      (node (ref "PCB1") (pin "A10") (pinfunction "A10_A10") (pintype "bidirectional"))
      (node (ref "SHARP3") (pin "1") (pinfunction "1_1") (pintype "passive"))
    )
    (net (code "58") (name "Net-(JP3-Pad4)") (class "Default")
      (node (ref "JP3") (pin "4") (pinfunction "4_4") (pintype "passive"))
      (node (ref "PCB1") (pin "A11") (pinfunction "A11_A11") (pintype "bidirectional"))
      (node (ref "SHARP4") (pin "1") (pinfunction "1_1") (pintype "passive"))
    )
    (net (code "59") (name "Net-(JP3-Pad5)") (class "Default")
      (node (ref "JP3") (pin "5") (pinfunction "5_5") (pintype "passive"))
      (node (ref "PCB1") (pin "A12") (pinfunction "A12_A12") (pintype "bidirectional"))
    )
    (net (code "60") (name "Net-(JP6-Pad9)") (class "Default")
      (node (ref "JP6") (pin "9") (pinfunction "9_9") (pintype "passive"))
      (node (ref "PCB1") (pin "28") (pinfunction "28_28") (pintype "bidirectional"))
    )
    (net (code "61") (name "Net-(JP6-Pad11)") (class "Default")
      (node (ref "JP6") (pin "11") (pinfunction "11_11") (pintype "passive"))
      (node (ref "PCB1") (pin "30") (pinfunction "30_30") (pintype "bidirectional"))
    )
    (net (code "62") (name "Net-(JP6-Pad13)") (class "Default")
      (node (ref "JP6") (pin "13") (pinfunction "13_13") (pintype "passive"))
      (node (ref "PCB1") (pin "32") (pinfunction "32_32") (pintype "bidirectional"))
    )
    (net (code "63") (name "Net-(JP6-Pad15)") (class "Default")
      (node (ref "JP6") (pin "15") (pinfunction "15_15") (pintype "passive"))
      (node (ref "PCB1") (pin "34") (pinfunction "34_34") (pintype "bidirectional"))
    )
    (net (code "64") (name "Net-(JP6-Pad20)") (class "Default")
      (node (ref "JP6") (pin "20") (pinfunction "20_20") (pintype "passive"))
      (node (ref "PCB1") (pin "39") (pinfunction "39_39") (pintype "bidirectional"))
    )
    (net (code "65") (name "Net-(JP6-Pad22)") (class "Default")
      (node (ref "JP6") (pin "22") (pinfunction "22_22") (pintype "passive"))
      (node (ref "PCB1") (pin "41") (pinfunction "41_41") (pintype "bidirectional"))
    )
    (net (code "66") (name "Net-(LED1-PadA)") (class "Default")
      (node (ref "LED1") (pin "A") (pinfunction "A_A") (pintype "passive"))
      (node (ref "RVO") (pin "2") (pinfunction "2_2") (pintype "passive"))
    )
    (net (code "67") (name "Net-(LED2-PadA)") (class "Default")
      (node (ref "LED2") (pin "A") (pinfunction "A_A") (pintype "passive"))
      (node (ref "R5V") (pin "2") (pinfunction "2_2") (pintype "passive"))
    )
    (net (code "68") (name "Net-(PCB1-(N{slash}C))") (class "Default")
      (node (ref "JP1") (pin "1") (pinfunction "1_1") (pintype "passive"))
      (node (ref "PCB1") (pin "N/C") (pinfunction "(N/C)_N/C") (pintype "bidirectional"))
    )
    (net (code "69") (name "Net-(PCB1-IOREF)") (class "Default")
      (node (ref "JP1") (pin "2") (pinfunction "2_2") (pintype "passive"))
      (node (ref "PCB1") (pin "I/OREF") (pinfunction "IOREF_I/OREF") (pintype "bidirectional"))
    )
    (net (code "70") (name "Net-(PCB1-PadAREF)") (class "Default")
      (node (ref "PCB1") (pin "AREF") (pinfunction "AREF_AREF") (pintype "bidirectional"))
      (node (ref "U$1") (pin "8") (pinfunction "8_8") (pintype "passive"))
    )
    (net (code "71") (name "Net-(PCB1-PadSCL1)") (class "Default")
      (node (ref "PCB1") (pin "SCL1") (pinfunction "SCL1_SCL1") (pintype "bidirectional"))
      (node (ref "U$1") (pin "10") (pinfunction "10_10") (pintype "passive"))
    )
    (net (code "72") (name "Net-(PCB1-PadSDA1)") (class "Default")
      (node (ref "PCB1") (pin "SDA1") (pinfunction "SDA1_SDA1") (pintype "bidirectional"))
      (node (ref "U$1") (pin "9") (pinfunction "9_9") (pintype "passive"))
    )
    (net (code "73") (name "Net-(RES-A1)") (class "Default")
      (node (ref "JP1") (pin "3") (pinfunction "3_3") (pintype "passive"))
      (node (ref "PCB1") (pin "RESET") (pinfunction "RESET_RESET") (pintype "bidirectional"))
      (node (ref "RES") (pin "4") (pinfunction "A1_4") (pintype "bidirectional"))
      (node (ref "RRES") (pin "1") (pinfunction "1_1") (pintype "passive"))
    )
    (net (code "74") (name "RX0") (class "Default")
      (node (ref "AC2MC") (pin "2") (pinfunction "2_2") (pintype "passive"))
      (node (ref "JP5") (pin "1") (pinfunction "1_1") (pintype "passive"))
      (node (ref "PCB1") (pin "0") (pinfunction "0(RX)_0") (pintype "bidirectional"))
    )
    (net (code "75") (name "RX1") (class "Default")
      (node (ref "IMU") (pin "5") (pinfunction "5_5") (pintype "passive"))
      (node (ref "JP4") (pin "3") (pinfunction "3_3") (pintype "passive"))
      (node (ref "PCB1") (pin "19") (pinfunction "19(RX1)_19") (pintype "bidirectional"))
    )
    (net (code "76") (name "RX2") (class "Default")
      (node (ref "JP4") (pin "5") (pinfunction "5_5") (pintype "passive"))
      (node (ref "LSA") (pin "1") (pinfunction "1_1") (pintype "passive"))
      (node (ref "PCB1") (pin "17") (pinfunction "17(RX2)_17") (pintype "bidirectional"))
    )
    (net (code "77") (name "RX3") (class "Default")
      (node (ref "ESP") (pin "2") (pinfunction "2_2") (pintype "passive"))
      (node (ref "JP4") (pin "7") (pinfunction "7_7") (pintype "passive"))
      (node (ref "LCD") (pin "3") (pinfunction "3_3") (pintype "passive"))
      (node (ref "PCB1") (pin "15") (pinfunction "15(RX3)_15") (pintype "bidirectional"))
    )
    (net (code "78") (name "SCL") (class "Default")
      (node (ref "I2C_1") (pin "1") (pinfunction "1_1") (pintype "passive"))
      (node (ref "I2C_2") (pin "1") (pinfunction "1_1") (pintype "passive"))
      (node (ref "I2C_3") (pin "1") (pinfunction "1_1") (pintype "passive"))
      (node (ref "JP4") (pin "1") (pinfunction "1_1") (pintype "passive"))
      (node (ref "PCB1") (pin "21") (pinfunction "21(SCL)_21") (pintype "bidirectional"))
      (node (ref "RSCL") (pin "2") (pinfunction "2_2") (pintype "passive"))
    )
    (net (code "79") (name "SDA") (class "Default")
      (node (ref "I2C_1") (pin "2") (pinfunction "2_2") (pintype "passive"))
      (node (ref "I2C_2") (pin "2") (pinfunction "2_2") (pintype "passive"))
      (node (ref "I2C_3") (pin "2") (pinfunction "2_2") (pintype "passive"))
      (node (ref "JP4") (pin "2") (pinfunction "2_2") (pintype "passive"))
      (node (ref "PCB1") (pin "20") (pinfunction "20(SDA)_20") (pintype "bidirectional"))
      (node (ref "RSDA") (pin "2") (pinfunction "2_2") (pintype "passive"))
    )
    (net (code "80") (name "TX0") (class "Default")
      (node (ref "AC2MC") (pin "3") (pinfunction "3_3") (pintype "passive"))
      (node (ref "JP5") (pin "2") (pinfunction "2_2") (pintype "passive"))
      (node (ref "PCB1") (pin "1") (pinfunction "1(TX)_1") (pintype "bidirectional"))
    )
    (net (code "81") (name "TX1") (class "Default")
      (node (ref "IMU") (pin "4") (pinfunction "4_4") (pintype "passive"))
      (node (ref "JP4") (pin "4") (pinfunction "4_4") (pintype "passive"))
      (node (ref "PCB1") (pin "18") (pinfunction "18(TX1)_18") (pintype "bidirectional"))
    )
    (net (code "82") (name "TX2") (class "Default")
      (node (ref "JP4") (pin "6") (pinfunction "6_6") (pintype "passive"))
      (node (ref "LSA") (pin "2") (pinfunction "2_2") (pintype "passive"))
      (node (ref "PCB1") (pin "16") (pinfunction "16(TX2)_16") (pintype "bidirectional"))
    )
    (net (code "83") (name "TX3") (class "Default")
      (node (ref "ESP") (pin "7") (pinfunction "7_7") (pintype "passive"))
      (node (ref "JP4") (pin "8") (pinfunction "8_8") (pintype "passive"))
      (node (ref "LCD") (pin "2") (pinfunction "2_2") (pintype "passive"))
      (node (ref "PCB1") (pin "14") (pinfunction "14(TX3)_14") (pintype "bidirectional"))
    )
    (net (code "84") (name "unconnected-(ESP-Pad3)") (class "Default")
      (node (ref "ESP") (pin "3") (pinfunction "3_3") (pintype "passive"))
    )
    (net (code "85") (name "unconnected-(ESP-Pad4)") (class "Default")
      (node (ref "ESP") (pin "4") (pinfunction "4_4") (pintype "passive"))
    )
    (net (code "86") (name "unconnected-(ESP-Pad6)") (class "Default")
      (node (ref "ESP") (pin "6") (pinfunction "6_6") (pintype "passive"))
    )
    (net (code "87") (name "unconnected-(I2-A0-Pad1)") (class "Default")
      (node (ref "I2") (pin "1") (pinfunction "A0_1") (pintype "bidirectional"))
    )
    (net (code "88") (name "unconnected-(I2-B1-Pad3)") (class "Default")
      (node (ref "I2") (pin "3") (pinfunction "B1_3") (pintype "bidirectional"))
    )
    (net (code "89") (name "unconnected-(I3-A0-Pad1)") (class "Default")
      (node (ref "I3") (pin "1") (pinfunction "A0_1") (pintype "bidirectional"))
    )
    (net (code "90") (name "unconnected-(I3-B1-Pad3)") (class "Default")
      (node (ref "I3") (pin "3") (pinfunction "B1_3") (pintype "bidirectional"))
    )
    (net (code "91") (name "unconnected-(IMU-Pad2)") (class "Default")
      (node (ref "IMU") (pin "2") (pinfunction "2_2") (pintype "passive"))
    )
    (net (code "92") (name "unconnected-(IMU-Pad6)") (class "Default")
      (node (ref "IMU") (pin "6") (pinfunction "6_6") (pintype "passive"))
    )
    (net (code "93") (name "unconnected-(PCB1-Pad+5V_)") (class "Default")
      (node (ref "PCB1") (pin "+5V_") (pinfunction "+5V__+5V_") (pintype "bidirectional"))
    )
    (net (code "94") (name "unconnected-(PCB1-Pad<PWR>+V)") (class "Default")
      (node (ref "PCB1") (pin "<PWR>+V") (pinfunction "<PWR>+V_<PWR>+V") (pintype "no_connect"))
    )
    (net (code "95") (name "unconnected-(PCB1-Pad<PWR>-V)") (class "Default")
      (node (ref "PCB1") (pin "<PWR>-V") (pinfunction "<PWR>-V_<PWR>-V") (pintype "no_connect"))
    )
    (net (code "96") (name "unconnected-(PCB1-Pad<USB>+V)") (class "Default")
      (node (ref "PCB1") (pin "<USB>+V") (pinfunction "<USB>+V_<USB>+V") (pintype "no_connect"))
    )
    (net (code "97") (name "unconnected-(PCB1-Pad<USB>D+)") (class "Default")
      (node (ref "PCB1") (pin "<USB>D+") (pinfunction "<USB>D+_<USB>D+") (pintype "no_connect"))
    )
    (net (code "98") (name "unconnected-(PCB1-Pad<USB>D-)") (class "Default")
      (node (ref "PCB1") (pin "<USB>D-") (pinfunction "<USB>D-_<USB>D-") (pintype "no_connect"))
    )
    (net (code "99") (name "unconnected-(PCB1-Pad<USB>GND)") (class "Default")
      (node (ref "PCB1") (pin "<USB>GND") (pinfunction "<USB>GND_<USB>GND") (pintype "no_connect"))
    )
    (net (code "100") (name "unconnected-(PCB1-PadGND__)") (class "Default")
      (node (ref "PCB1") (pin "GND__") (pinfunction "GND___GND__") (pintype "bidirectional"))
    )
    (net (code "101") (name "unconnected-(PCB1-PadMISO)") (class "Default")
      (node (ref "PCB1") (pin "MISO") (pinfunction "MISO_MISO") (pintype "bidirectional"))
    )
    (net (code "102") (name "unconnected-(PCB1-PadMOSI)") (class "Default")
      (node (ref "PCB1") (pin "MOSI") (pinfunction "MOSI_MOSI") (pintype "bidirectional"))
    )
    (net (code "103") (name "unconnected-(PCB1-PadRESET.)") (class "Default")
      (node (ref "PCB1") (pin "RESET.") (pinfunction "RESET._RESET.") (pintype "bidirectional"))
    )
    (net (code "104") (name "unconnected-(PCB1-PadSCK)") (class "Default")
      (node (ref "PCB1") (pin "SCK") (pinfunction "SCK_SCK") (pintype "bidirectional"))
    )
    (net (code "105") (name "unconnected-(RES-A0-Pad1)") (class "Default")
      (node (ref "RES") (pin "1") (pinfunction "A0_1") (pintype "bidirectional"))
    )
    (net (code "106") (name "unconnected-(RES-B1-Pad3)") (class "Default")
      (node (ref "RES") (pin "3") (pinfunction "B1_3") (pintype "bidirectional"))
    )
  )
)
